# 31.net
KiCad netlist of a schematic drawn in Altium Designer
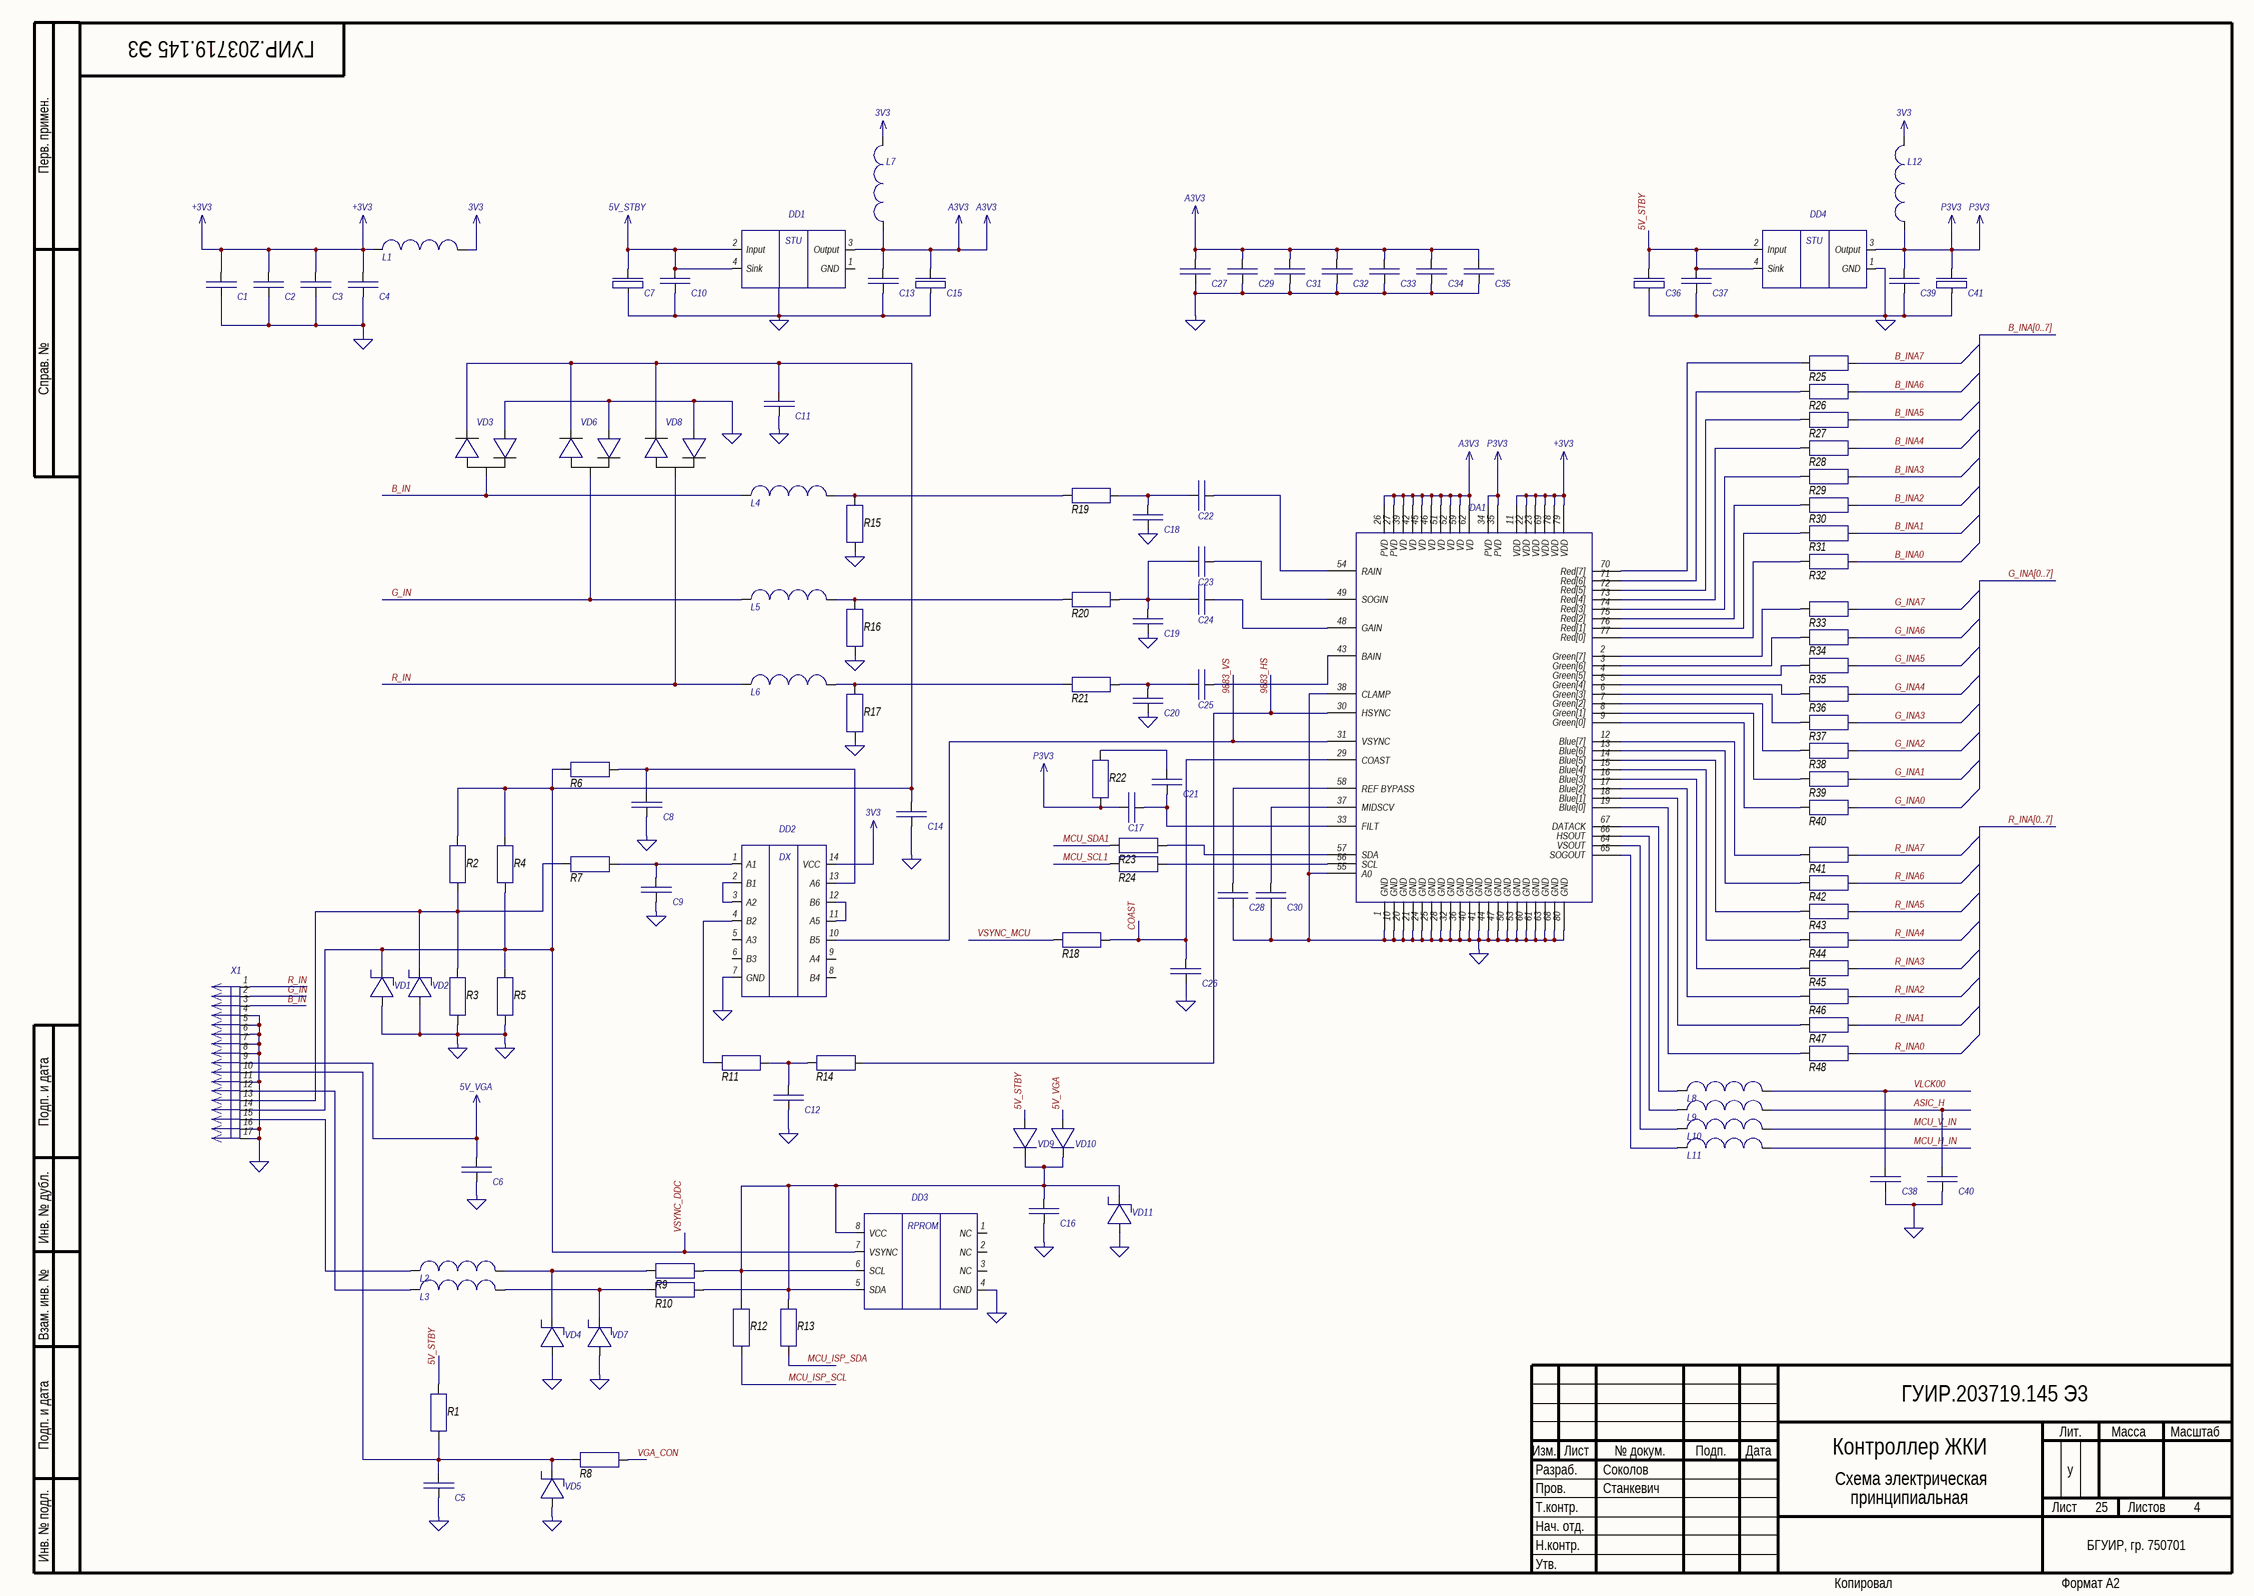
[diagram p0: 31.SchDoc]

(export (version "E")
  (design (tool "Eeschema 10.0.6"))
  (components
    (comp (ref "C1")
      (value "Capacitor")
      (footprint "cap_electro_13")
      (libsource (lib "31_lib") (part "Capacitor"))
    )
    (comp (ref "C2")
      (value "Capacitor")
      (footprint "cap_electro_13")
      (libsource (lib "31_lib") (part "Capacitor"))
    )
    (comp (ref "C3")
      (value "Capacitor")
      (footprint "cap_electro_13")
      (libsource (lib "31_lib") (part "Capacitor"))
    )
    (comp (ref "C4")
      (value "Capacitor")
      (footprint "cap_electro_13")
      (libsource (lib "31_lib") (part "Capacitor"))
    )
    (comp (ref "C5")
      (value "Capacitor")
      (footprint "cap_electro_13")
      (libsource (lib "31_lib") (part "Capacitor"))
    )
    (comp (ref "C6")
      (value "Capacitor")
      (footprint "cap_electro_13")
      (libsource (lib "31_lib") (part "Capacitor"))
    )
    (comp (ref "C7")
      (value "TuningCapacitor")
      (footprint "31_lib:Cap_tantal_D")
      (libsource (lib "31_lib") (part "TuningCapacitor"))
    )
    (comp (ref "C8")
      (value "Capacitor")
      (footprint "cap_electro_13")
      (libsource (lib "31_lib") (part "Capacitor"))
    )
    (comp (ref "C9")
      (value "Capacitor")
      (footprint "cap_electro_13")
      (libsource (lib "31_lib") (part "Capacitor"))
    )
    (comp (ref "C10")
      (value "Capacitor")
      (footprint "cap_electro_13")
      (libsource (lib "31_lib") (part "Capacitor"))
    )
    (comp (ref "C11")
      (value "Capacitor")
      (footprint "cap_electro_13")
      (libsource (lib "31_lib") (part "Capacitor"))
    )
    (comp (ref "C12")
      (value "Capacitor")
      (footprint "cap_electro_13")
      (libsource (lib "31_lib") (part "Capacitor"))
    )
    (comp (ref "C13")
      (value "Capacitor")
      (footprint "cap_electro_13")
      (libsource (lib "31_lib") (part "Capacitor"))
    )
    (comp (ref "C14")
      (value "Capacitor")
      (footprint "cap_electro_13")
      (libsource (lib "31_lib") (part "Capacitor"))
    )
    (comp (ref "C15")
      (value "TuningCapacitor")
      (footprint "31_lib:Cap_tantal_D")
      (libsource (lib "31_lib") (part "TuningCapacitor"))
    )
    (comp (ref "C16")
      (value "Capacitor")
      (footprint "cap_electro_13")
      (libsource (lib "31_lib") (part "Capacitor"))
    )
    (comp (ref "C17")
      (value "Capacitor")
      (footprint "cap_electro_13")
      (libsource (lib "31_lib") (part "Capacitor"))
    )
    (comp (ref "C18")
      (value "Capacitor")
      (footprint "cap_electro_13")
      (libsource (lib "31_lib") (part "Capacitor"))
    )
    (comp (ref "C19")
      (value "Capacitor")
      (footprint "cap_electro_13")
      (libsource (lib "31_lib") (part "Capacitor"))
    )
    (comp (ref "C20")
      (value "Capacitor")
      (footprint "cap_electro_13")
      (libsource (lib "31_lib") (part "Capacitor"))
    )
    (comp (ref "C21")
      (value "Capacitor")
      (footprint "cap_electro_13")
      (libsource (lib "31_lib") (part "Capacitor"))
    )
    (comp (ref "C22")
      (value "Capacitor")
      (footprint "cap_electro_13")
      (libsource (lib "31_lib") (part "Capacitor"))
    )
    (comp (ref "C23")
      (value "Capacitor")
      (footprint "cap_electro_13")
      (libsource (lib "31_lib") (part "Capacitor"))
    )
    (comp (ref "C24")
      (value "Capacitor")
      (footprint "cap_electro_13")
      (libsource (lib "31_lib") (part "Capacitor"))
    )
    (comp (ref "C25")
      (value "Capacitor")
      (footprint "cap_electro_13")
      (libsource (lib "31_lib") (part "Capacitor"))
    )
    (comp (ref "C26")
      (value "Capacitor")
      (footprint "cap_electro_13")
      (libsource (lib "31_lib") (part "Capacitor"))
    )
    (comp (ref "C27")
      (value "Capacitor")
      (footprint "cap_electro_13")
      (libsource (lib "31_lib") (part "Capacitor"))
    )
    (comp (ref "C28")
      (value "Capacitor")
      (footprint "cap_electro_13")
      (libsource (lib "31_lib") (part "Capacitor"))
    )
    (comp (ref "C29")
      (value "Capacitor")
      (footprint "cap_electro_13")
      (libsource (lib "31_lib") (part "Capacitor"))
    )
    (comp (ref "C30")
      (value "Capacitor")
      (footprint "cap_electro_13")
      (libsource (lib "31_lib") (part "Capacitor"))
    )
    (comp (ref "C31")
      (value "Capacitor")
      (footprint "cap_electro_13")
      (libsource (lib "31_lib") (part "Capacitor"))
    )
    (comp (ref "C32")
      (value "Capacitor")
      (footprint "cap_electro_13")
      (libsource (lib "31_lib") (part "Capacitor"))
    )
    (comp (ref "C33")
      (value "Capacitor")
      (footprint "cap_electro_13")
      (libsource (lib "31_lib") (part "Capacitor"))
    )
    (comp (ref "C34")
      (value "Capacitor")
      (footprint "cap_electro_13")
      (libsource (lib "31_lib") (part "Capacitor"))
    )
    (comp (ref "C35")
      (value "Capacitor")
      (footprint "cap_electro_13")
      (libsource (lib "31_lib") (part "Capacitor"))
    )
    (comp (ref "C36")
      (value "TuningCapacitor")
      (footprint "31_lib:Cap_tantal_D")
      (libsource (lib "31_lib") (part "TuningCapacitor"))
    )
    (comp (ref "C37")
      (value "Capacitor")
      (footprint "cap_electro_13")
      (libsource (lib "31_lib") (part "Capacitor"))
    )
    (comp (ref "C38")
      (value "Capacitor")
      (footprint "cap_electro_13")
      (libsource (lib "31_lib") (part "Capacitor"))
    )
    (comp (ref "C39")
      (value "Capacitor")
      (footprint "cap_electro_13")
      (libsource (lib "31_lib") (part "Capacitor"))
    )
    (comp (ref "C40")
      (value "Capacitor")
      (footprint "cap_electro_13")
      (libsource (lib "31_lib") (part "Capacitor"))
    )
    (comp (ref "C41")
      (value "TuningCapacitor")
      (footprint "31_lib:Cap_tantal_D")
      (libsource (lib "31_lib") (part "TuningCapacitor"))
    )
    (comp (ref "DA1")
      (value "AD9883ABSTZ-140")
      (footprint "31_lib:ST_80_2_ADI")
      (fields (field (name "COPYRIGHT") "Copyright (C) 2018 Accelerated Designs. All rights reserved"))
      (libsource (lib "31_lib") (part "AD9883ABSTZ-140"))
    )
    (comp (ref "DD1")
      (value "AIC1732")
      (footprint "31_lib:AIC1732(SOT-89)")
      (libsource (lib "31_lib") (part "AIC1732"))
    )
    (comp (ref "DD2")
      (value "74LVX14")
      (footprint "31_lib:74LVX14(SO-14)")
      (libsource (lib "31_lib") (part "74LVX14"))
    )
    (comp (ref "DD3") (value "24C21") (footprint "31_lib:24Cxx") (libsource (lib "31_lib") (part "24C21")))
    (comp (ref "DD4")
      (value "AIC1732")
      (footprint "31_lib:AIC1732(SOT-89)")
      (libsource (lib "31_lib") (part "AIC1732"))
    )
    (comp (ref "L1")
      (value "Inductor")
      (footprint "31_lib:inductor")
      (libsource (lib "31_lib") (part "Inductor"))
    )
    (comp (ref "L2")
      (value "Inductor")
      (footprint "31_lib:inductor")
      (libsource (lib "31_lib") (part "Inductor"))
    )
    (comp (ref "L3")
      (value "Inductor")
      (footprint "31_lib:inductor")
      (libsource (lib "31_lib") (part "Inductor"))
    )
    (comp (ref "L4")
      (value "Inductor")
      (footprint "31_lib:inductor")
      (libsource (lib "31_lib") (part "Inductor"))
    )
    (comp (ref "L5")
      (value "Inductor")
      (footprint "31_lib:inductor")
      (libsource (lib "31_lib") (part "Inductor"))
    )
    (comp (ref "L6")
      (value "Inductor")
      (footprint "31_lib:inductor")
      (libsource (lib "31_lib") (part "Inductor"))
    )
    (comp (ref "L7")
      (value "Inductor")
      (footprint "31_lib:inductor")
      (libsource (lib "31_lib") (part "Inductor"))
    )
    (comp (ref "L8")
      (value "Inductor")
      (footprint "31_lib:inductor")
      (libsource (lib "31_lib") (part "Inductor"))
    )
    (comp (ref "L9")
      (value "Inductor")
      (footprint "31_lib:inductor")
      (libsource (lib "31_lib") (part "Inductor"))
    )
    (comp (ref "L10")
      (value "Inductor")
      (footprint "31_lib:inductor")
      (libsource (lib "31_lib") (part "Inductor"))
    )
    (comp (ref "L11")
      (value "Inductor")
      (footprint "31_lib:inductor")
      (libsource (lib "31_lib") (part "Inductor"))
    )
    (comp (ref "L12")
      (value "Inductor")
      (footprint "31_lib:inductor")
      (libsource (lib "31_lib") (part "Inductor"))
    )
    (comp (ref "R1")
      (value "Resistor")
      (footprint "lab_7_footprints:R_1206")
      (libsource (lib "31_lib") (part "Resistor"))
    )
    (comp (ref "R2")
      (value "Resistor")
      (footprint "lab_7_footprints:R_1206")
      (libsource (lib "31_lib") (part "Resistor"))
    )
    (comp (ref "R3")
      (value "Resistor")
      (footprint "lab_7_footprints:R_1206")
      (libsource (lib "31_lib") (part "Resistor"))
    )
    (comp (ref "R4")
      (value "Resistor")
      (footprint "lab_7_footprints:R_1206")
      (libsource (lib "31_lib") (part "Resistor"))
    )
    (comp (ref "R5")
      (value "Resistor")
      (footprint "lab_7_footprints:R_1206")
      (libsource (lib "31_lib") (part "Resistor"))
    )
    (comp (ref "R6")
      (value "Resistor")
      (footprint "lab_7_footprints:R_1206")
      (libsource (lib "31_lib") (part "Resistor"))
    )
    (comp (ref "R7")
      (value "Resistor")
      (footprint "lab_7_footprints:R_1206")
      (libsource (lib "31_lib") (part "Resistor"))
    )
    (comp (ref "R8")
      (value "Resistor")
      (footprint "lab_7_footprints:R_1206")
      (libsource (lib "31_lib") (part "Resistor"))
    )
    (comp (ref "R9")
      (value "Resistor")
      (footprint "lab_7_footprints:R_1206")
      (libsource (lib "31_lib") (part "Resistor"))
    )
    (comp (ref "R10")
      (value "Resistor")
      (footprint "lab_7_footprints:R_1206")
      (libsource (lib "31_lib") (part "Resistor"))
    )
    (comp (ref "R11")
      (value "Resistor")
      (footprint "lab_7_footprints:R_1206")
      (libsource (lib "31_lib") (part "Resistor"))
    )
    (comp (ref "R12")
      (value "Resistor")
      (footprint "lab_7_footprints:R_1206")
      (libsource (lib "31_lib") (part "Resistor"))
    )
    (comp (ref "R13")
      (value "Resistor")
      (footprint "lab_7_footprints:R_1206")
      (libsource (lib "31_lib") (part "Resistor"))
    )
    (comp (ref "R14")
      (value "Resistor")
      (footprint "lab_7_footprints:R_1206")
      (libsource (lib "31_lib") (part "Resistor"))
    )
    (comp (ref "R15")
      (value "Resistor")
      (footprint "lab_7_footprints:R_1206")
      (libsource (lib "31_lib") (part "Resistor"))
    )
    (comp (ref "R16")
      (value "Resistor")
      (footprint "lab_7_footprints:R_1206")
      (libsource (lib "31_lib") (part "Resistor"))
    )
    (comp (ref "R17")
      (value "Resistor")
      (footprint "lab_7_footprints:R_1206")
      (libsource (lib "31_lib") (part "Resistor"))
    )
    (comp (ref "R18")
      (value "Resistor")
      (footprint "lab_7_footprints:R_1206")
      (libsource (lib "31_lib") (part "Resistor"))
    )
    (comp (ref "R19")
      (value "Resistor")
      (footprint "lab_7_footprints:R_1206")
      (libsource (lib "31_lib") (part "Resistor"))
    )
    (comp (ref "R20")
      (value "Resistor")
      (footprint "lab_7_footprints:R_1206")
      (libsource (lib "31_lib") (part "Resistor"))
    )
    (comp (ref "R21")
      (value "Resistor")
      (footprint "lab_7_footprints:R_1206")
      (libsource (lib "31_lib") (part "Resistor"))
    )
    (comp (ref "R22")
      (value "Resistor")
      (footprint "lab_7_footprints:R_1206")
      (libsource (lib "31_lib") (part "Resistor"))
    )
    (comp (ref "R23")
      (value "Resistor")
      (footprint "lab_7_footprints:R_1206")
      (libsource (lib "31_lib") (part "Resistor"))
    )
    (comp (ref "R24")
      (value "Resistor")
      (footprint "lab_7_footprints:R_1206")
      (libsource (lib "31_lib") (part "Resistor"))
    )
    (comp (ref "R25")
      (value "Resistor")
      (footprint "lab_7_footprints:R_1206")
      (libsource (lib "31_lib") (part "Resistor"))
    )
    (comp (ref "R26")
      (value "Resistor")
      (footprint "lab_7_footprints:R_1206")
      (libsource (lib "31_lib") (part "Resistor"))
    )
    (comp (ref "R27")
      (value "Resistor")
      (footprint "lab_7_footprints:R_1206")
      (libsource (lib "31_lib") (part "Resistor"))
    )
    (comp (ref "R28")
      (value "Resistor")
      (footprint "lab_7_footprints:R_1206")
      (libsource (lib "31_lib") (part "Resistor"))
    )
    (comp (ref "R29")
      (value "Resistor")
      (footprint "lab_7_footprints:R_1206")
      (libsource (lib "31_lib") (part "Resistor"))
    )
    (comp (ref "R30")
      (value "Resistor")
      (footprint "lab_7_footprints:R_1206")
      (libsource (lib "31_lib") (part "Resistor"))
    )
    (comp (ref "R31")
      (value "Resistor")
      (footprint "lab_7_footprints:R_1206")
      (libsource (lib "31_lib") (part "Resistor"))
    )
    (comp (ref "R32")
      (value "Resistor")
      (footprint "lab_7_footprints:R_1206")
      (libsource (lib "31_lib") (part "Resistor"))
    )
    (comp (ref "R33")
      (value "Resistor")
      (footprint "lab_7_footprints:R_1206")
      (libsource (lib "31_lib") (part "Resistor"))
    )
    (comp (ref "R34")
      (value "Resistor")
      (footprint "lab_7_footprints:R_1206")
      (libsource (lib "31_lib") (part "Resistor"))
    )
    (comp (ref "R35")
      (value "Resistor")
      (footprint "lab_7_footprints:R_1206")
      (libsource (lib "31_lib") (part "Resistor"))
    )
    (comp (ref "R36")
      (value "Resistor")
      (footprint "lab_7_footprints:R_1206")
      (libsource (lib "31_lib") (part "Resistor"))
    )
    (comp (ref "R37")
      (value "Resistor")
      (footprint "lab_7_footprints:R_1206")
      (libsource (lib "31_lib") (part "Resistor"))
    )
    (comp (ref "R38")
      (value "Resistor")
      (footprint "lab_7_footprints:R_1206")
      (libsource (lib "31_lib") (part "Resistor"))
    )
    (comp (ref "R39")
      (value "Resistor")
      (footprint "lab_7_footprints:R_1206")
      (libsource (lib "31_lib") (part "Resistor"))
    )
    (comp (ref "R40")
      (value "Resistor")
      (footprint "lab_7_footprints:R_1206")
      (libsource (lib "31_lib") (part "Resistor"))
    )
    (comp (ref "R41")
      (value "Resistor")
      (footprint "lab_7_footprints:R_1206")
      (libsource (lib "31_lib") (part "Resistor"))
    )
    (comp (ref "R42")
      (value "Resistor")
      (footprint "lab_7_footprints:R_1206")
      (libsource (lib "31_lib") (part "Resistor"))
    )
    (comp (ref "R43")
      (value "Resistor")
      (footprint "lab_7_footprints:R_1206")
      (libsource (lib "31_lib") (part "Resistor"))
    )
    (comp (ref "R44")
      (value "Resistor")
      (footprint "lab_7_footprints:R_1206")
      (libsource (lib "31_lib") (part "Resistor"))
    )
    (comp (ref "R45")
      (value "Resistor")
      (footprint "lab_7_footprints:R_1206")
      (libsource (lib "31_lib") (part "Resistor"))
    )
    (comp (ref "R46")
      (value "Resistor")
      (footprint "lab_7_footprints:R_1206")
      (libsource (lib "31_lib") (part "Resistor"))
    )
    (comp (ref "R47")
      (value "Resistor")
      (footprint "lab_7_footprints:R_1206")
      (libsource (lib "31_lib") (part "Resistor"))
    )
    (comp (ref "R48")
      (value "Resistor")
      (footprint "lab_7_footprints:R_1206")
      (libsource (lib "31_lib") (part "Resistor"))
    )
    (comp (ref "VD1")
      (value "DiodeSchottky")
      (footprint "lab_7_footprints:zener_diode")
      (libsource (lib "31_lib") (part "DiodeSchottky"))
    )
    (comp (ref "VD2")
      (value "DiodeSchottky")
      (footprint "lab_7_footprints:zener_diode")
      (libsource (lib "31_lib") (part "DiodeSchottky"))
    )
    (comp (ref "VD3") (value "BAV99") (footprint "31_lib:BAV99") (libsource (lib "31_lib") (part "BAV99")))
    (comp (ref "VD4")
      (value "DiodeSchottky")
      (footprint "lab_7_footprints:zener_diode")
      (libsource (lib "31_lib") (part "DiodeSchottky"))
    )
    (comp (ref "VD5")
      (value "DiodeSchottky")
      (footprint "lab_7_footprints:zener_diode")
      (libsource (lib "31_lib") (part "DiodeSchottky"))
    )
    (comp (ref "VD6") (value "BAV99") (footprint "31_lib:BAV99") (libsource (lib "31_lib") (part "BAV99")))
    (comp (ref "VD7")
      (value "DiodeSchottky")
      (footprint "lab_7_footprints:zener_diode")
      (libsource (lib "31_lib") (part "DiodeSchottky"))
    )
    (comp (ref "VD8") (value "BAV99") (footprint "31_lib:BAV99") (libsource (lib "31_lib") (part "BAV99")))
    (comp (ref "VD9")
      (value "Diode")
      (footprint "lab_7_footprints:zener_diode")
      (libsource (lib "31_lib") (part "Diode"))
    )
    (comp (ref "VD10")
      (value "Diode")
      (footprint "lab_7_footprints:zener_diode")
      (libsource (lib "31_lib") (part "Diode"))
    )
    (comp (ref "VD11")
      (value "DiodeSchottky")
      (footprint "lab_7_footprints:zener_diode")
      (libsource (lib "31_lib") (part "DiodeSchottky"))
    )
    (comp (ref "X1")
      (value "DB-15")
      (footprint "31_lib:VGA")
      (libsource (lib "31_lib") (part "VGA_connector"))
    )
  )
  (nets
    (net (code "1") (name "+3V3") (class "Default")
      (node (ref "C1") (pin "1") (pinfunction "1_1") (pintype "passive"))
      (node (ref "C2") (pin "1") (pinfunction "1_1") (pintype "passive"))
      (node (ref "C3") (pin "1") (pinfunction "1_1") (pintype "passive"))
      (node (ref "C4") (pin "1") (pinfunction "1_1") (pintype "passive"))
      (node (ref "DA1") (pin "11") (pinfunction "VDD_11") (pintype "power_in"))
      (node (ref "DA1") (pin "22") (pinfunction "VDD_22") (pintype "power_in"))
      (node (ref "DA1") (pin "23") (pinfunction "VDD_23") (pintype "power_in"))
      (node (ref "DA1") (pin "69") (pinfunction "VDD_69") (pintype "power_in"))
      (node (ref "DA1") (pin "78") (pinfunction "VDD_78") (pintype "power_in"))
      (node (ref "DA1") (pin "79") (pinfunction "VDD_79") (pintype "power_in"))
      (node (ref "L1") (pin "1") (pinfunction "1_1") (pintype "passive"))
    )
    (net (code "2") (name "/9883_HS") (class "Default")
      (node (ref "DA1") (pin "30") (pinfunction "HSYNC_30") (pintype "passive"))
      (node (ref "R14") (pin "2") (pinfunction "2_2") (pintype "passive"))
    )
    (net (code "3") (name "/9883_VS") (class "Default")
      (node (ref "DA1") (pin "31") (pinfunction "VSYNC_31") (pintype "passive"))
      (node (ref "DD2") (pin "10") (pinfunction "B5_10") (pintype "passive"))
    )
    (net (code "4") (name "/ASIC_H") (class "Default")
      (node (ref "C40") (pin "1") (pinfunction "1_1") (pintype "passive"))
      (node (ref "L9") (pin "2") (pinfunction "2_2") (pintype "passive"))
    )
    (net (code "5") (name "/B_IN") (class "Default")
      (node (ref "L4") (pin "1") (pinfunction "1_1") (pintype "passive"))
      (node (ref "VD3") (pin "3") (pinfunction "3_3") (pintype "passive"))
      (node (ref "X1") (pin "3") (pinfunction "3_3") (pintype "passive"))
    )
    (net (code "6") (name "/B_INA0") (class "Default")
      (node (ref "R32") (pin "2") (pinfunction "2_2") (pintype "passive"))
    )
    (net (code "7") (name "/B_INA1") (class "Default")
      (node (ref "R31") (pin "2") (pinfunction "2_2") (pintype "passive"))
    )
    (net (code "8") (name "/B_INA2") (class "Default")
      (node (ref "R30") (pin "2") (pinfunction "2_2") (pintype "passive"))
    )
    (net (code "9") (name "/B_INA3") (class "Default")
      (node (ref "R29") (pin "2") (pinfunction "2_2") (pintype "passive"))
    )
    (net (code "10") (name "/B_INA4") (class "Default")
      (node (ref "R28") (pin "2") (pinfunction "2_2") (pintype "passive"))
    )
    (net (code "11") (name "/B_INA5") (class "Default")
      (node (ref "R27") (pin "2") (pinfunction "2_2") (pintype "passive"))
    )
    (net (code "12") (name "/B_INA6") (class "Default")
      (node (ref "R26") (pin "2") (pinfunction "2_2") (pintype "passive"))
    )
    (net (code "13") (name "/B_INA7") (class "Default")
      (node (ref "R25") (pin "2") (pinfunction "2_2") (pintype "passive"))
    )
    (net (code "15") (name "/COAST") (class "Default")
      (node (ref "C26") (pin "2") (pinfunction "2_2") (pintype "passive"))
      (node (ref "DA1") (pin "29") (pinfunction "COAST_29") (pintype "passive"))
      (node (ref "R18") (pin "2") (pinfunction "2_2") (pintype "passive"))
    )
    (net (code "16") (name "/G_IN") (class "Default")
      (node (ref "L5") (pin "1") (pinfunction "1_1") (pintype "passive"))
      (node (ref "VD6") (pin "3") (pinfunction "3_3") (pintype "passive"))
      (node (ref "X1") (pin "2") (pinfunction "2_2") (pintype "passive"))
    )
    (net (code "17") (name "/G_INA0") (class "Default")
      (node (ref "R40") (pin "2") (pinfunction "2_2") (pintype "passive"))
    )
    (net (code "18") (name "/G_INA1") (class "Default")
      (node (ref "R39") (pin "2") (pinfunction "2_2") (pintype "passive"))
    )
    (net (code "19") (name "/G_INA2") (class "Default")
      (node (ref "R38") (pin "2") (pinfunction "2_2") (pintype "passive"))
    )
    (net (code "20") (name "/G_INA3") (class "Default")
      (node (ref "R37") (pin "2") (pinfunction "2_2") (pintype "passive"))
    )
    (net (code "21") (name "/G_INA4") (class "Default")
      (node (ref "R36") (pin "2") (pinfunction "2_2") (pintype "passive"))
    )
    (net (code "22") (name "/G_INA5") (class "Default")
      (node (ref "R35") (pin "2") (pinfunction "2_2") (pintype "passive"))
    )
    (net (code "23") (name "/G_INA6") (class "Default")
      (node (ref "R34") (pin "2") (pinfunction "2_2") (pintype "passive"))
    )
    (net (code "24") (name "/G_INA7") (class "Default")
      (node (ref "R33") (pin "2") (pinfunction "2_2") (pintype "passive"))
    )
    (net (code "26") (name "/MCU_H_IN") (class "Default")
      (node (ref "L11") (pin "2") (pinfunction "2_2") (pintype "passive"))
    )
    (net (code "27") (name "/MCU_ISP_SCL") (class "Default")
      (node (ref "R12") (pin "1") (pinfunction "1_1") (pintype "passive"))
    )
    (net (code "28") (name "/MCU_ISP_SDA") (class "Default")
      (node (ref "R13") (pin "1") (pinfunction "1_1") (pintype "passive"))
    )
    (net (code "29") (name "/MCU_SCL1") (class "Default")
      (node (ref "R24") (pin "1") (pinfunction "1_1") (pintype "passive"))
    )
    (net (code "30") (name "/MCU_SDA1") (class "Default")
      (node (ref "R23") (pin "1") (pinfunction "1_1") (pintype "passive"))
    )
    (net (code "31") (name "/MCU_V_IN") (class "Default")
      (node (ref "L10") (pin "2") (pinfunction "2_2") (pintype "passive"))
    )
    (net (code "32") (name "/R_IN") (class "Default")
      (node (ref "L6") (pin "1") (pinfunction "1_1") (pintype "passive"))
      (node (ref "VD8") (pin "3") (pinfunction "3_3") (pintype "passive"))
      (node (ref "X1") (pin "1") (pinfunction "1_1") (pintype "passive"))
    )
    (net (code "33") (name "/R_INA0") (class "Default")
      (node (ref "R48") (pin "2") (pinfunction "2_2") (pintype "passive"))
    )
    (net (code "34") (name "/R_INA1") (class "Default")
      (node (ref "R47") (pin "2") (pinfunction "2_2") (pintype "passive"))
    )
    (net (code "35") (name "/R_INA2") (class "Default")
      (node (ref "R46") (pin "2") (pinfunction "2_2") (pintype "passive"))
    )
    (net (code "36") (name "/R_INA3") (class "Default")
      (node (ref "R45") (pin "2") (pinfunction "2_2") (pintype "passive"))
    )
    (net (code "37") (name "/R_INA4") (class "Default")
      (node (ref "R44") (pin "2") (pinfunction "2_2") (pintype "passive"))
    )
    (net (code "38") (name "/R_INA5") (class "Default")
      (node (ref "R43") (pin "2") (pinfunction "2_2") (pintype "passive"))
    )
    (net (code "39") (name "/R_INA6") (class "Default")
      (node (ref "R42") (pin "2") (pinfunction "2_2") (pintype "passive"))
    )
    (net (code "40") (name "/R_INA7") (class "Default")
      (node (ref "R41") (pin "2") (pinfunction "2_2") (pintype "passive"))
    )
    (net (code "42") (name "/VGA_CON") (class "Default")
      (node (ref "R8") (pin "2") (pinfunction "2_2") (pintype "passive"))
    )
    (net (code "43") (name "/VLCK00") (class "Default")
      (node (ref "C38") (pin "1") (pinfunction "1_1") (pintype "passive"))
      (node (ref "L8") (pin "2") (pinfunction "2_2") (pintype "passive"))
    )
    (net (code "44") (name "/VSYNC_DDC") (class "Default")
      (node (ref "C11") (pin "1") (pinfunction "1_1") (pintype "passive"))
      (node (ref "C14") (pin "1") (pinfunction "1_1") (pintype "passive"))
      (node (ref "DD3") (pin "7") (pinfunction "VSYNC_7") (pintype "passive"))
      (node (ref "R2") (pin "2") (pinfunction "2_2") (pintype "passive"))
      (node (ref "R4") (pin "1") (pinfunction "1_1") (pintype "passive"))
      (node (ref "R4") (pin "2") (pinfunction "2_2") (pintype "passive"))
      (node (ref "R5") (pin "2") (pinfunction "2_2") (pintype "passive"))
      (node (ref "R6") (pin "1") (pinfunction "1_1") (pintype "passive"))
      (node (ref "VD1") (pin "2") (pinfunction "2_2") (pintype "passive"))
      (node (ref "VD3") (pin "2") (pinfunction "2_2") (pintype "passive"))
      (node (ref "VD6") (pin "2") (pinfunction "2_2") (pintype "passive"))
      (node (ref "VD8") (pin "2") (pinfunction "2_2") (pintype "passive"))
      (node (ref "X1") (pin "14") (pinfunction "14_14") (pintype "passive"))
    )
    (net (code "45") (name "/VSYNC_MCU") (class "Default")
      (node (ref "R18") (pin "1") (pinfunction "1_1") (pintype "passive"))
    )
    (net (code "46") (name "3V3") (class "Default")
      (node (ref "DD2") (pin "14") (pinfunction "VCC_14") (pintype "passive"))
      (node (ref "L1") (pin "2") (pinfunction "2_2") (pintype "passive"))
      (node (ref "L12") (pin "2") (pinfunction "2_2") (pintype "passive"))
      (node (ref "L7") (pin "2") (pinfunction "2_2") (pintype "passive"))
    )
    (net (code "47") (name "5V_STBY") (class "Default")
      (node (ref "C10") (pin "1") (pinfunction "1_1") (pintype "passive"))
      (node (ref "C36") (pin "1") (pinfunction "1_1") (pintype "passive"))
      (node (ref "C37") (pin "1") (pinfunction "1_1") (pintype "passive"))
      (node (ref "C7") (pin "1") (pinfunction "1_1") (pintype "passive"))
      (node (ref "DD1") (pin "2") (pinfunction "Input_2") (pintype "passive"))
      (node (ref "DD1") (pin "4") (pinfunction "Sink_4") (pintype "passive"))
      (node (ref "DD4") (pin "2") (pinfunction "Input_2") (pintype "passive"))
      (node (ref "DD4") (pin "4") (pinfunction "Sink_4") (pintype "passive"))
      (node (ref "R1") (pin "2") (pinfunction "2_2") (pintype "passive"))
      (node (ref "VD9") (pin "1") (pinfunction "1_1") (pintype "passive"))
    )
    (net (code "48") (name "5V_VGA") (class "Default")
      (node (ref "C6") (pin "2") (pinfunction "2_2") (pintype "passive"))
      (node (ref "VD10") (pin "1") (pinfunction "1_1") (pintype "passive"))
      (node (ref "X1") (pin "9") (pinfunction "9_9") (pintype "passive"))
    )
    (net (code "49") (name "A3V3") (class "Default")
      (node (ref "C13") (pin "1") (pinfunction "1_1") (pintype "passive"))
      (node (ref "C15") (pin "1") (pinfunction "1_1") (pintype "passive"))
      (node (ref "C27") (pin "1") (pinfunction "1_1") (pintype "passive"))
      (node (ref "C29") (pin "1") (pinfunction "1_1") (pintype "passive"))
      (node (ref "C31") (pin "1") (pinfunction "1_1") (pintype "passive"))
      (node (ref "C32") (pin "1") (pinfunction "1_1") (pintype "passive"))
      (node (ref "C33") (pin "1") (pinfunction "1_1") (pintype "passive"))
      (node (ref "C34") (pin "1") (pinfunction "1_1") (pintype "passive"))
      (node (ref "C35") (pin "1") (pinfunction "1_1") (pintype "passive"))
      (node (ref "DA1") (pin "26") (pinfunction "PVD_26") (pintype "power_in"))
      (node (ref "DA1") (pin "27") (pinfunction "PVD_27") (pintype "power_in"))
      (node (ref "DA1") (pin "39") (pinfunction "VD_39") (pintype "power_in"))
      (node (ref "DA1") (pin "42") (pinfunction "VD_42") (pintype "power_in"))
      (node (ref "DA1") (pin "45") (pinfunction "VD_45") (pintype "power_in"))
      (node (ref "DA1") (pin "46") (pinfunction "VD_46") (pintype "power_in"))
      (node (ref "DA1") (pin "51") (pinfunction "VD_51") (pintype "power_in"))
      (node (ref "DA1") (pin "52") (pinfunction "VD_52") (pintype "power_in"))
      (node (ref "DA1") (pin "59") (pinfunction "VD_59") (pintype "power_in"))
      (node (ref "DA1") (pin "62") (pinfunction "VD_62") (pintype "power_in"))
      (node (ref "DD1") (pin "3") (pinfunction "Output_3") (pintype "passive"))
      (node (ref "L7") (pin "1") (pinfunction "1_1") (pintype "passive"))
    )
    (net (code "50") (name "GND") (class "Default")
      (node (ref "C1") (pin "2") (pinfunction "2_2") (pintype "passive"))
      (node (ref "C10") (pin "2") (pinfunction "2_2") (pintype "passive"))
      (node (ref "C11") (pin "2") (pinfunction "2_2") (pintype "passive"))
      (node (ref "C12") (pin "2") (pinfunction "2_2") (pintype "passive"))
      (node (ref "C13") (pin "2") (pinfunction "2_2") (pintype "passive"))
      (node (ref "C14") (pin "2") (pinfunction "2_2") (pintype "passive"))
      (node (ref "C15") (pin "2") (pinfunction "2_2") (pintype "passive"))
      (node (ref "C16") (pin "2") (pinfunction "2_2") (pintype "passive"))
      (node (ref "C18") (pin "2") (pinfunction "2_2") (pintype "passive"))
      (node (ref "C19") (pin "2") (pinfunction "2_2") (pintype "passive"))
      (node (ref "C2") (pin "2") (pinfunction "2_2") (pintype "passive"))
      (node (ref "C20") (pin "2") (pinfunction "2_2") (pintype "passive"))
      (node (ref "C26") (pin "1") (pinfunction "1_1") (pintype "passive"))
      (node (ref "C27") (pin "2") (pinfunction "2_2") (pintype "passive"))
      (node (ref "C28") (pin "1") (pinfunction "1_1") (pintype "passive"))
      (node (ref "C29") (pin "2") (pinfunction "2_2") (pintype "passive"))
      (node (ref "C3") (pin "2") (pinfunction "2_2") (pintype "passive"))
      (node (ref "C30") (pin "1") (pinfunction "1_1") (pintype "passive"))
      (node (ref "C31") (pin "2") (pinfunction "2_2") (pintype "passive"))
      (node (ref "C32") (pin "2") (pinfunction "2_2") (pintype "passive"))
      (node (ref "C33") (pin "2") (pinfunction "2_2") (pintype "passive"))
      (node (ref "C34") (pin "2") (pinfunction "2_2") (pintype "passive"))
      (node (ref "C35") (pin "2") (pinfunction "2_2") (pintype "passive"))
      (node (ref "C36") (pin "2") (pinfunction "2_2") (pintype "passive"))
      (node (ref "C37") (pin "2") (pinfunction "2_2") (pintype "passive"))
      (node (ref "C38") (pin "2") (pinfunction "2_2") (pintype "passive"))
      (node (ref "C39") (pin "2") (pinfunction "2_2") (pintype "passive"))
      (node (ref "C4") (pin "2") (pinfunction "2_2") (pintype "passive"))
      (node (ref "C40") (pin "2") (pinfunction "2_2") (pintype "passive"))
      (node (ref "C41") (pin "2") (pinfunction "2_2") (pintype "passive"))
      (node (ref "C5") (pin "2") (pinfunction "2_2") (pintype "passive"))
      (node (ref "C6") (pin "1") (pinfunction "1_1") (pintype "passive"))
      (node (ref "C7") (pin "2") (pinfunction "2_2") (pintype "passive"))
      (node (ref "C8") (pin "2") (pinfunction "2_2") (pintype "passive"))
      (node (ref "C9") (pin "2") (pinfunction "2_2") (pintype "passive"))
      (node (ref "DA1") (pin "1") (pinfunction "GND_1") (pintype "passive"))
      (node (ref "DA1") (pin "10") (pinfunction "GND_10") (pintype "passive"))
      (node (ref "DA1") (pin "20") (pinfunction "GND_20") (pintype "passive"))
      (node (ref "DA1") (pin "21") (pinfunction "GND_21") (pintype "passive"))
      (node (ref "DA1") (pin "24") (pinfunction "GND_24") (pintype "passive"))
      (node (ref "DA1") (pin "25") (pinfunction "GND_25") (pintype "passive"))
      (node (ref "DA1") (pin "28") (pinfunction "GND_28") (pintype "passive"))
      (node (ref "DA1") (pin "32") (pinfunction "GND_32") (pintype "passive"))
      (node (ref "DA1") (pin "36") (pinfunction "GND_36") (pintype "passive"))
      (node (ref "DA1") (pin "38") (pinfunction "CLAMP_38") (pintype "passive"))
      (node (ref "DA1") (pin "40") (pinfunction "GND_40") (pintype "passive"))
      (node (ref "DA1") (pin "41") (pinfunction "GND_41") (pintype "passive"))
      (node (ref "DA1") (pin "44") (pinfunction "GND_44") (pintype "passive"))
      (node (ref "DA1") (pin "47") (pinfunction "GND_47") (pintype "passive"))
      (node (ref "DA1") (pin "50") (pinfunction "GND_50") (pintype "passive"))
      (node (ref "DA1") (pin "53") (pinfunction "GND_53") (pintype "passive"))
      (node (ref "DA1") (pin "55") (pinfunction "A0_55") (pintype "passive"))
      (node (ref "DA1") (pin "60") (pinfunction "GND_60") (pintype "passive"))
      (node (ref "DA1") (pin "61") (pinfunction "GND_61") (pintype "passive"))
      (node (ref "DA1") (pin "63") (pinfunction "GND_63") (pintype "passive"))
      (node (ref "DA1") (pin "68") (pinfunction "GND_68") (pintype "passive"))
      (node (ref "DA1") (pin "80") (pinfunction "GND_80") (pintype "passive"))
      (node (ref "DD2") (pin "7") (pinfunction "GND_7") (pintype "passive"))
      (node (ref "DD3") (pin "4") (pinfunction "GND_4") (pintype "passive"))
      (node (ref "DD4") (pin "1") (pinfunction "GND_1") (pintype "passive"))
      (node (ref "R15") (pin "1") (pinfunction "1_1") (pintype "passive"))
      (node (ref "R16") (pin "1") (pinfunction "1_1") (pintype "passive"))
      (node (ref "R17") (pin "1") (pinfunction "1_1") (pintype "passive"))
      (node (ref "R3") (pin "1") (pinfunction "1_1") (pintype "passive"))
      (node (ref "R5") (pin "1") (pinfunction "1_1") (pintype "passive"))
      (node (ref "VD1") (pin "1") (pinfunction "1_1") (pintype "passive"))
      (node (ref "VD11") (pin "1") (pinfunction "1_1") (pintype "passive"))
      (node (ref "VD2") (pin "1") (pinfunction "1_1") (pintype "passive"))
      (node (ref "VD3") (pin "1") (pinfunction "1_1") (pintype "passive"))
      (node (ref "VD4") (pin "1") (pinfunction "1_1") (pintype "passive"))
      (node (ref "VD5") (pin "1") (pinfunction "1_1") (pintype "passive"))
      (node (ref "VD6") (pin "1") (pinfunction "1_1") (pintype "passive"))
      (node (ref "VD7") (pin "1") (pinfunction "1_1") (pintype "passive"))
      (node (ref "VD8") (pin "1") (pinfunction "1_1") (pintype "passive"))
      (node (ref "X1") (pin "11") (pinfunction "11_11") (pintype "passive"))
      (node (ref "X1") (pin "16") (pinfunction "16_16") (pintype "passive"))
      (node (ref "X1") (pin "17") (pinfunction "17_17") (pintype "passive"))
      (node (ref "X1") (pin "4") (pinfunction "4_4") (pintype "passive"))
      (node (ref "X1") (pin "5") (pinfunction "5_5") (pintype "passive"))
      (node (ref "X1") (pin "6") (pinfunction "6_6") (pintype "passive"))
      (node (ref "X1") (pin "7") (pinfunction "7_7") (pintype "passive"))
      (node (ref "X1") (pin "8") (pinfunction "8_8") (pintype "passive"))
    )
    (net (code "51") (name "Net-(C5-Pad1)") (class "Default")
      (node (ref "C5") (pin "1") (pinfunction "1_1") (pintype "passive"))
      (node (ref "R1") (pin "1") (pinfunction "1_1") (pintype "passive"))
      (node (ref "R8") (pin "1") (pinfunction "1_1") (pintype "passive"))
      (node (ref "VD5") (pin "2") (pinfunction "2_2") (pintype "passive"))
      (node (ref "X1") (pin "10") (pinfunction "10_10") (pintype "passive"))
    )
    (net (code "52") (name "Net-(C12-Pad1)") (class "Default")
      (node (ref "C12") (pin "1") (pinfunction "1_1") (pintype "passive"))
      (node (ref "R11") (pin "2") (pinfunction "2_2") (pintype "passive"))
      (node (ref "R14") (pin "1") (pinfunction "1_1") (pintype "passive"))
    )
    (net (code "53") (name "Net-(C18-Pad1)") (class "Default")
      (node (ref "C18") (pin "1") (pinfunction "1_1") (pintype "passive"))
      (node (ref "C22") (pin "2") (pinfunction "2_2") (pintype "passive"))
      (node (ref "R19") (pin "2") (pinfunction "2_2") (pintype "passive"))
    )
    (net (code "54") (name "Net-(C19-Pad1)") (class "Default")
      (node (ref "C19") (pin "1") (pinfunction "1_1") (pintype "passive"))
      (node (ref "C23") (pin "2") (pinfunction "2_2") (pintype "passive"))
      (node (ref "C24") (pin "2") (pinfunction "2_2") (pintype "passive"))
      (node (ref "R20") (pin "2") (pinfunction "2_2") (pintype "passive"))
    )
    (net (code "55") (name "Net-(C20-Pad1)") (class "Default")
      (node (ref "C20") (pin "1") (pinfunction "1_1") (pintype "passive"))
      (node (ref "C25") (pin "2") (pinfunction "2_2") (pintype "passive"))
      (node (ref "R21") (pin "2") (pinfunction "2_2") (pintype "passive"))
    )
    (net (code "56") (name "Net-(C21-Pad2)") (class "Default")
      (node (ref "C21") (pin "2") (pinfunction "2_2") (pintype "passive"))
      (node (ref "R22") (pin "2") (pinfunction "2_2") (pintype "passive"))
    )
    (net (code "57") (name "Net-(DA1-BAIN)") (class "Default")
      (node (ref "C25") (pin "1") (pinfunction "1_1") (pintype "passive"))
      (node (ref "DA1") (pin "43") (pinfunction "BAIN_43") (pintype "passive"))
    )
    (net (code "58") (name "Net-(DA1-Blue[0])") (class "Default")
      (node (ref "DA1") (pin "19") (pinfunction "Blue[0]_19") (pintype "passive"))
      (node (ref "R48") (pin "1") (pinfunction "1_1") (pintype "passive"))
    )
    (net (code "59") (name "Net-(DA1-Blue[1])") (class "Default")
      (node (ref "DA1") (pin "18") (pinfunction "Blue[1]_18") (pintype "passive"))
      (node (ref "R47") (pin "1") (pinfunction "1_1") (pintype "passive"))
    )
    (net (code "60") (name "Net-(DA1-Blue[2])") (class "Default")
      (node (ref "DA1") (pin "17") (pinfunction "Blue[2]_17") (pintype "passive"))
      (node (ref "R46") (pin "1") (pinfunction "1_1") (pintype "passive"))
    )
    (net (code "61") (name "Net-(DA1-Blue[3])") (class "Default")
      (node (ref "DA1") (pin "16") (pinfunction "Blue[3]_16") (pintype "passive"))
      (node (ref "R45") (pin "1") (pinfunction "1_1") (pintype "passive"))
    )
    (net (code "62") (name "Net-(DA1-Blue[4])") (class "Default")
      (node (ref "DA1") (pin "15") (pinfunction "Blue[4]_15") (pintype "passive"))
      (node (ref "R44") (pin "1") (pinfunction "1_1") (pintype "passive"))
    )
    (net (code "63") (name "Net-(DA1-Blue[5])") (class "Default")
      (node (ref "DA1") (pin "14") (pinfunction "Blue[5]_14") (pintype "passive"))
      (node (ref "R43") (pin "1") (pinfunction "1_1") (pintype "passive"))
    )
    (net (code "64") (name "Net-(DA1-Blue[6])") (class "Default")
      (node (ref "DA1") (pin "13") (pinfunction "Blue[6]_13") (pintype "passive"))
      (node (ref "R42") (pin "1") (pinfunction "1_1") (pintype "passive"))
    )
    (net (code "65") (name "Net-(DA1-Blue[7])") (class "Default")
      (node (ref "DA1") (pin "12") (pinfunction "Blue[7]_12") (pintype "passive"))
      (node (ref "R41") (pin "1") (pinfunction "1_1") (pintype "passive"))
    )
    (net (code "66") (name "Net-(DA1-DATACK)") (class "Default")
      (node (ref "DA1") (pin "67") (pinfunction "DATACK_67") (pintype "passive"))
      (node (ref "L8") (pin "1") (pinfunction "1_1") (pintype "passive"))
    )
    (net (code "67") (name "Net-(DA1-FILT)") (class "Default")
      (node (ref "C17") (pin "1") (pinfunction "1_1") (pintype "passive"))
      (node (ref "C21") (pin "1") (pinfunction "1_1") (pintype "passive"))
      (node (ref "DA1") (pin "33") (pinfunction "FILT_33") (pintype "passive"))
    )
    (net (code "68") (name "Net-(DA1-GAIN)") (class "Default")
      (node (ref "C24") (pin "1") (pinfunction "1_1") (pintype "passive"))
      (node (ref "DA1") (pin "48") (pinfunction "GAIN_48") (pintype "passive"))
    )
    (net (code "69") (name "Net-(DA1-Green[0])") (class "Default")
      (node (ref "DA1") (pin "9") (pinfunction "Green[0]_9") (pintype "passive"))
      (node (ref "R40") (pin "1") (pinfunction "1_1") (pintype "passive"))
    )
    (net (code "70") (name "Net-(DA1-Green[1])") (class "Default")
      (node (ref "DA1") (pin "8") (pinfunction "Green[1]_8") (pintype "passive"))
      (node (ref "R39") (pin "1") (pinfunction "1_1") (pintype "passive"))
    )
    (net (code "71") (name "Net-(DA1-Green[2])") (class "Default")
      (node (ref "DA1") (pin "7") (pinfunction "Green[2]_7") (pintype "passive"))
      (node (ref "R38") (pin "1") (pinfunction "1_1") (pintype "passive"))
    )
    (net (code "72") (name "Net-(DA1-Green[3])") (class "Default")
      (node (ref "DA1") (pin "6") (pinfunction "Green[3]_6") (pintype "passive"))
      (node (ref "R37") (pin "1") (pinfunction "1_1") (pintype "passive"))
    )
    (net (code "73") (name "Net-(DA1-Green[4])") (class "Default")
      (node (ref "DA1") (pin "5") (pinfunction "Green[4]_5") (pintype "passive"))
      (node (ref "R36") (pin "1") (pinfunction "1_1") (pintype "passive"))
    )
    (net (code "74") (name "Net-(DA1-Green[5])") (class "Default")
      (node (ref "DA1") (pin "4") (pinfunction "Green[5]_4") (pintype "passive"))
      (node (ref "R35") (pin "1") (pinfunction "1_1") (pintype "passive"))
    )
    (net (code "75") (name "Net-(DA1-Green[6])") (class "Default")
      (node (ref "DA1") (pin "3") (pinfunction "Green[6]_3") (pintype "passive"))
      (node (ref "R34") (pin "1") (pinfunction "1_1") (pintype "passive"))
    )
    (net (code "76") (name "Net-(DA1-Green[7])") (class "Default")
      (node (ref "DA1") (pin "2") (pinfunction "Green[7]_2") (pintype "passive"))
      (node (ref "R33") (pin "1") (pinfunction "1_1") (pintype "passive"))
    )
    (net (code "77") (name "Net-(DA1-HSOUT)") (class "Default")
      (node (ref "DA1") (pin "66") (pinfunction "HSOUT_66") (pintype "passive"))
      (node (ref "L9") (pin "1") (pinfunction "1_1") (pintype "passive"))
    )
    (net (code "78") (name "Net-(DA1-MIDSCV)") (class "Default")
      (node (ref "C30") (pin "2") (pinfunction "2_2") (pintype "passive"))
      (node (ref "DA1") (pin "37") (pinfunction "MIDSCV_37") (pintype "passive"))
    )
    (net (code "79") (name "Net-(DA1-RAIN)") (class "Default")
      (node (ref "C22") (pin "1") (pinfunction "1_1") (pintype "passive"))
      (node (ref "DA1") (pin "54") (pinfunction "RAIN_54") (pintype "passive"))
    )
    (net (code "80") (name "Net-(DA1-REF_BYPASS)") (class "Default")
      (node (ref "C28") (pin "2") (pinfunction "2_2") (pintype "passive"))
      (node (ref "DA1") (pin "58") (pinfunction "REF_BYPASS_58") (pintype "passive"))
    )
    (net (code "81") (name "Net-(DA1-Red[0])") (class "Default")
      (node (ref "DA1") (pin "77") (pinfunction "Red[0]_77") (pintype "passive"))
      (node (ref "R32") (pin "1") (pinfunction "1_1") (pintype "passive"))
    )
    (net (code "82") (name "Net-(DA1-Red[1])") (class "Default")
      (node (ref "DA1") (pin "76") (pinfunction "Red[1]_76") (pintype "passive"))
      (node (ref "R31") (pin "1") (pinfunction "1_1") (pintype "passive"))
    )
    (net (code "83") (name "Net-(DA1-Red[2])") (class "Default")
      (node (ref "DA1") (pin "75") (pinfunction "Red[2]_75") (pintype "passive"))
      (node (ref "R30") (pin "1") (pinfunction "1_1") (pintype "passive"))
    )
    (net (code "84") (name "Net-(DA1-Red[3])") (class "Default")
      (node (ref "DA1") (pin "74") (pinfunction "Red[3]_74") (pintype "passive"))
      (node (ref "R29") (pin "1") (pinfunction "1_1") (pintype "passive"))
    )
    (net (code "85") (name "Net-(DA1-Red[4])") (class "Default")
      (node (ref "DA1") (pin "73") (pinfunction "Red[4]_73") (pintype "passive"))
      (node (ref "R28") (pin "1") (pinfunction "1_1") (pintype "passive"))
    )
    (net (code "86") (name "Net-(DA1-Red[5])") (class "Default")
      (node (ref "DA1") (pin "72") (pinfunction "Red[5]_72") (pintype "passive"))
      (node (ref "R27") (pin "1") (pinfunction "1_1") (pintype "passive"))
    )
    (net (code "87") (name "Net-(DA1-Red[6])") (class "Default")
      (node (ref "DA1") (pin "71") (pinfunction "Red[6]_71") (pintype "passive"))
      (node (ref "R26") (pin "1") (pinfunction "1_1") (pintype "passive"))
    )
    (net (code "88") (name "Net-(DA1-Red[7])") (class "Default")
      (node (ref "DA1") (pin "70") (pinfunction "Red[7]_70") (pintype "passive"))
      (node (ref "R25") (pin "1") (pinfunction "1_1") (pintype "passive"))
    )
    (net (code "89") (name "Net-(DA1-SCL)") (class "Default")
      (node (ref "DA1") (pin "56") (pinfunction "SCL_56") (pintype "passive"))
      (node (ref "R24") (pin "2") (pinfunction "2_2") (pintype "passive"))
    )
    (net (code "90") (name "Net-(DA1-SDA)") (class "Default")
      (node (ref "DA1") (pin "57") (pinfunction "SDA_57") (pintype "passive"))
      (node (ref "R23") (pin "2") (pinfunction "2_2") (pintype "passive"))
    )
    (net (code "91") (name "Net-(DA1-SOGIN)") (class "Default")
      (node (ref "C23") (pin "1") (pinfunction "1_1") (pintype "passive"))
      (node (ref "DA1") (pin "49") (pinfunction "SOGIN_49") (pintype "passive"))
    )
    (net (code "92") (name "Net-(DA1-SOGOUT)") (class "Default")
      (node (ref "DA1") (pin "65") (pinfunction "SOGOUT_65") (pintype "passive"))
      (node (ref "L11") (pin "1") (pinfunction "1_1") (pintype "passive"))
    )
    (net (code "93") (name "Net-(DA1-VSOUT)") (class "Default")
      (node (ref "DA1") (pin "64") (pinfunction "VSOUT_64") (pintype "passive"))
      (node (ref "L10") (pin "1") (pinfunction "1_1") (pintype "passive"))
    )
    (net (code "94") (name "Net-(DD2-A1)") (class "Default")
      (node (ref "C9") (pin "1") (pinfunction "1_1") (pintype "passive"))
      (node (ref "DD2") (pin "1") (pinfunction "A1_1") (pintype "passive"))
      (node (ref "R7") (pin "2") (pinfunction "2_2") (pintype "passive"))
    )
    (net (code "95") (name "Net-(DD2-A2)") (class "Default")
      (node (ref "DD2") (pin "2") (pinfunction "B1_2") (pintype "passive"))
      (node (ref "DD2") (pin "3") (pinfunction "A2_3") (pintype "passive"))
    )
    (net (code "96") (name "Net-(DD2-A5)") (class "Default")
      (node (ref "DD2") (pin "11") (pinfunction "A5_11") (pintype "passive"))
      (node (ref "DD2") (pin "12") (pinfunction "B6_12") (pintype "passive"))
    )
    (net (code "97") (name "Net-(DD2-A6)") (class "Default")
      (node (ref "C8") (pin "1") (pinfunction "1_1") (pintype "passive"))
      (node (ref "DD2") (pin "13") (pinfunction "A6_13") (pintype "passive"))
      (node (ref "R6") (pin "2") (pinfunction "2_2") (pintype "passive"))
    )
    (net (code "98") (name "Net-(DD2-B2)") (class "Default")
      (node (ref "DD2") (pin "4") (pinfunction "B2_4") (pintype "passive"))
      (node (ref "R11") (pin "1") (pinfunction "1_1") (pintype "passive"))
    )
    (net (code "99") (name "Net-(DD3-SCL)") (class "Default")
      (node (ref "C16") (pin "1") (pinfunction "1_1") (pintype "passive"))
      (node (ref "DD3") (pin "5") (pinfunction "SDA_5") (pintype "passive"))
      (node (ref "DD3") (pin "6") (pinfunction "SCL_6") (pintype "passive"))
      (node (ref "DD3") (pin "8") (pinfunction "VCC_8") (pintype "passive"))
      (node (ref "R10") (pin "2") (pinfunction "2_2") (pintype "passive"))
      (node (ref "R12") (pin "2") (pinfunction "2_2") (pintype "passive"))
      (node (ref "R13") (pin "2") (pinfunction "2_2") (pintype "passive"))
      (node (ref "R9") (pin "2") (pinfunction "2_2") (pintype "passive"))
      (node (ref "VD10") (pin "2") (pinfunction "2_2") (pintype "passive"))
      (node (ref "VD11") (pin "2") (pinfunction "2_2") (pintype "passive"))
      (node (ref "VD9") (pin "2") (pinfunction "2_2") (pintype "passive"))
    )
    (net (code "100") (name "Net-(L2-Pad1)") (class "Default")
      (node (ref "L2") (pin "1") (pinfunction "1_1") (pintype "passive"))
      (node (ref "X1") (pin "15") (pinfunction "15_15") (pintype "passive"))
    )
    (net (code "101") (name "Net-(L2-Pad2)") (class "Default")
      (node (ref "L2") (pin "2") (pinfunction "2_2") (pintype "passive"))
      (node (ref "R9") (pin "1") (pinfunction "1_1") (pintype "passive"))
      (node (ref "VD4") (pin "2") (pinfunction "2_2") (pintype "passive"))
    )
    (net (code "102") (name "Net-(L3-Pad1)") (class "Default")
      (node (ref "L3") (pin "1") (pinfunction "1_1") (pintype "passive"))
      (node (ref "X1") (pin "12") (pinfunction "12_12") (pintype "passive"))
    )
    (net (code "103") (name "Net-(L3-Pad2)") (class "Default")
      (node (ref "L3") (pin "2") (pinfunction "2_2") (pintype "passive"))
      (node (ref "R10") (pin "1") (pinfunction "1_1") (pintype "passive"))
      (node (ref "VD7") (pin "2") (pinfunction "2_2") (pintype "passive"))
    )
    (net (code "104") (name "Net-(L4-Pad2)") (class "Default")
      (node (ref "L4") (pin "2") (pinfunction "2_2") (pintype "passive"))
      (node (ref "R15") (pin "2") (pinfunction "2_2") (pintype "passive"))
      (node (ref "R19") (pin "1") (pinfunction "1_1") (pintype "passive"))
    )
    (net (code "105") (name "Net-(L5-Pad2)") (class "Default")
      (node (ref "L5") (pin "2") (pinfunction "2_2") (pintype "passive"))
      (node (ref "R16") (pin "2") (pinfunction "2_2") (pintype "passive"))
      (node (ref "R20") (pin "1") (pinfunction "1_1") (pintype "passive"))
    )
    (net (code "106") (name "Net-(L6-Pad2)") (class "Default")
      (node (ref "L6") (pin "2") (pinfunction "2_2") (pintype "passive"))
      (node (ref "R17") (pin "2") (pinfunction "2_2") (pintype "passive"))
      (node (ref "R21") (pin "1") (pinfunction "1_1") (pintype "passive"))
    )
    (net (code "107") (name "Net-(R2-Pad1)") (class "Default")
      (node (ref "R2") (pin "1") (pinfunction "1_1") (pintype "passive"))
      (node (ref "R3") (pin "2") (pinfunction "2_2") (pintype "passive"))
      (node (ref "R7") (pin "1") (pinfunction "1_1") (pintype "passive"))
      (node (ref "VD2") (pin "2") (pinfunction "2_2") (pintype "passive"))
      (node (ref "X1") (pin "13") (pinfunction "13_13") (pintype "passive"))
    )
    (net (code "108") (name "P3V3") (class "Default")
      (node (ref "C17") (pin "2") (pinfunction "2_2") (pintype "passive"))
      (node (ref "C39") (pin "1") (pinfunction "1_1") (pintype "passive"))
      (node (ref "C41") (pin "1") (pinfunction "1_1") (pintype "passive"))
      (node (ref "DA1") (pin "34") (pinfunction "PVD_34") (pintype "power_in"))
      (node (ref "DA1") (pin "35") (pinfunction "PVD_35") (pintype "power_in"))
      (node (ref "DD4") (pin "3") (pinfunction "Output_3") (pintype "passive"))
      (node (ref "L12") (pin "1") (pinfunction "1_1") (pintype "passive"))
      (node (ref "R22") (pin "1") (pinfunction "1_1") (pintype "passive"))
    )
    (net (code "109") (name "unconnected-(DD1-GND-Pad1)") (class "Default")
      (node (ref "DD1") (pin "1") (pinfunction "GND_1") (pintype "passive"))
    )
    (net (code "110") (name "unconnected-(DD2-A3-Pad5)") (class "Default")
      (node (ref "DD2") (pin "5") (pinfunction "A3_5") (pintype "passive"))
    )
    (net (code "111") (name "unconnected-(DD2-A4-Pad9)") (class "Default")
      (node (ref "DD2") (pin "9") (pinfunction "A4_9") (pintype "passive"))
    )
    (net (code "112") (name "unconnected-(DD2-B3-Pad6)") (class "Default")
      (node (ref "DD2") (pin "6") (pinfunction "B3_6") (pintype "passive"))
    )
    (net (code "113") (name "unconnected-(DD2-B4-Pad8)") (class "Default")
      (node (ref "DD2") (pin "8") (pinfunction "B4_8") (pintype "passive"))
    )
    (net (code "114") (name "unconnected-(DD3-NC-Pad1)") (class "Default")
      (node (ref "DD3") (pin "1") (pinfunction "NC_1") (pintype "passive"))
    )
    (net (code "115") (name "unconnected-(DD3-NC-Pad2)") (class "Default")
      (node (ref "DD3") (pin "2") (pinfunction "NC_2") (pintype "passive"))
    )
    (net (code "116") (name "unconnected-(DD3-NC-Pad3)") (class "Default")
      (node (ref "DD3") (pin "3") (pinfunction "NC_3") (pintype "passive"))
    )
  )
)
